# LDConnector_v2.net
KiCad netlist of a schematic drawn in EAGLE
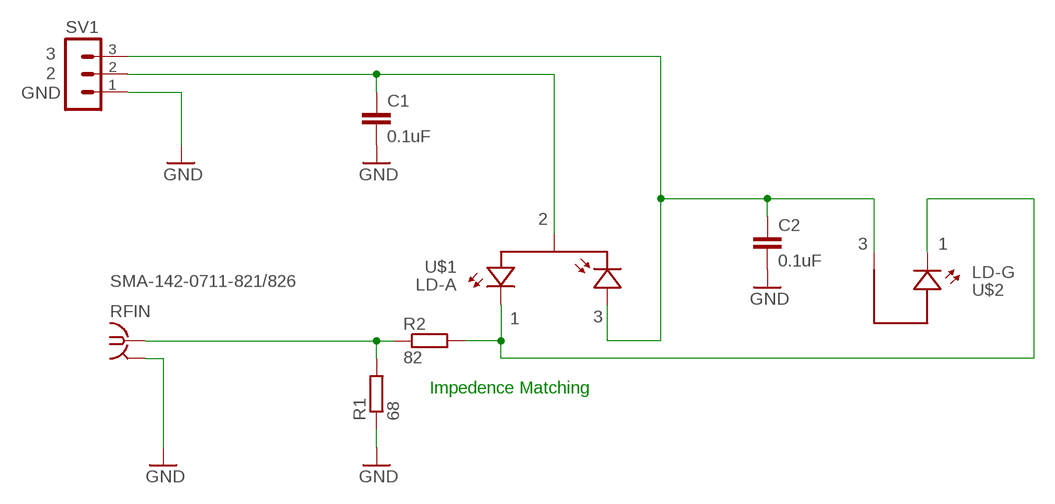
[diagram p0: schematic, sheet 1]

(export (version "E")
  (design (tool "Eeschema 10.0.6"))
  (components
    (comp (ref "C1")
      (value "0.1uF")
      (footprint "eagle-import:C0603")
      (libsource (lib "eagle-import") (part "C-EUC0603"))
    )
    (comp (ref "C2")
      (value "0.1uF")
      (footprint "eagle-import:C0603")
      (libsource (lib "eagle-import") (part "C-EUC0603"))
    )
    (comp (ref "R1")
      (value "68")
      (footprint "eagle-import:R0603")
      (libsource (lib "eagle-import") (part "R-EU_R0603"))
    )
    (comp (ref "R2")
      (value "82")
      (footprint "eagle-import:R0603")
      (libsource (lib "eagle-import") (part "R-EU_R0603"))
    )
    (comp (ref "RFIN")
      (value "SMA-142-0711-821/826")
      (footprint "eagle-import:J502-ND-142-0711-821_826")
      (fields (field (name "MF") "JOHNSON COMPONENTS") (field (name "MPN") "142-0711-821"))
      (libsource (lib "eagle-import") (part "SMA-142-0711-821/826"))
    )
    (comp (ref "SV1")
      (value "MA03-1")
      (footprint "eagle-import:MA03-1")
      (libsource (lib "eagle-import") (part "MA03-1"))
    )
    (comp (ref "U$1")
      (value "LD-A")
      (footprint "eagle-import:TYPEA")
      (libsource (lib "eagle-import") (part "LD-A"))
    )
    (comp (ref "U$2")
      (value "LD-G")
      (footprint "eagle-import:TYPEG")
      (libsource (lib "eagle-import") (part "LD-G"))
    )
  )
  (nets
    (net (code "1") (name "GND") (class "Default")
      (node (ref "C1") (pin "2") (pinfunction "2_2") (pintype "passive"))
      (node (ref "C2") (pin "2") (pinfunction "2_2") (pintype "passive"))
      (node (ref "R1") (pin "1") (pinfunction "1_1") (pintype "passive"))
      (node (ref "RFIN") (pin "G@1") (pinfunction "2_G@1") (pintype "passive"))
      (node (ref "RFIN") (pin "G@2") (pinfunction "2_G@2") (pintype "passive"))
      (node (ref "RFIN") (pin "G@3") (pinfunction "2_G@3") (pintype "passive"))
      (node (ref "RFIN") (pin "G@4") (pinfunction "2_G@4") (pintype "passive"))
      (node (ref "SV1") (pin "1") (pinfunction "1_1") (pintype "passive"))
    )
    (net (code "2") (name "Net-(R1-Pad2)") (class "Default")
      (node (ref "R1") (pin "2") (pinfunction "2_2") (pintype "passive"))
      (node (ref "R2") (pin "1") (pinfunction "1_1") (pintype "passive"))
      (node (ref "RFIN") (pin "1") (pinfunction "1_1") (pintype "passive"))
    )
    (net (code "3") (name "Net-(U$1-LDA-PDC)") (class "Default")
      (node (ref "C1") (pin "1") (pinfunction "1_1") (pintype "passive"))
      (node (ref "SV1") (pin "2") (pinfunction "2_2") (pintype "passive"))
      (node (ref "U$1") (pin "2-PDC-LDA") (pinfunction "LDA-PDC_2-PDC-LDA") (pintype "passive"))
    )
    (net (code "4") (name "Net-(U$1-LDC)") (class "Default")
      (node (ref "R2") (pin "2") (pinfunction "2_2") (pintype "passive"))
      (node (ref "U$1") (pin "1-LDC") (pinfunction "LDC_1-LDC") (pintype "passive"))
      (node (ref "U$2") (pin "1-LDC") (pinfunction "LDC_1-LDC") (pintype "passive"))
    )
    (net (code "5") (name "Net-(U$1-PDA)") (class "Default")
      (node (ref "C2") (pin "1") (pinfunction "1_1") (pintype "passive"))
      (node (ref "SV1") (pin "3") (pinfunction "3_3") (pintype "passive"))
      (node (ref "U$1") (pin "3-PDA") (pinfunction "PDA_3-PDA") (pintype "passive"))
      (node (ref "U$2") (pin "3-LDA") (pinfunction "LDA_3-LDA") (pintype "passive"))
    )
  )
)
